# TensorSensor_Driver_DC.net
KiCad netlist of a schematic drawn in Altium Designer
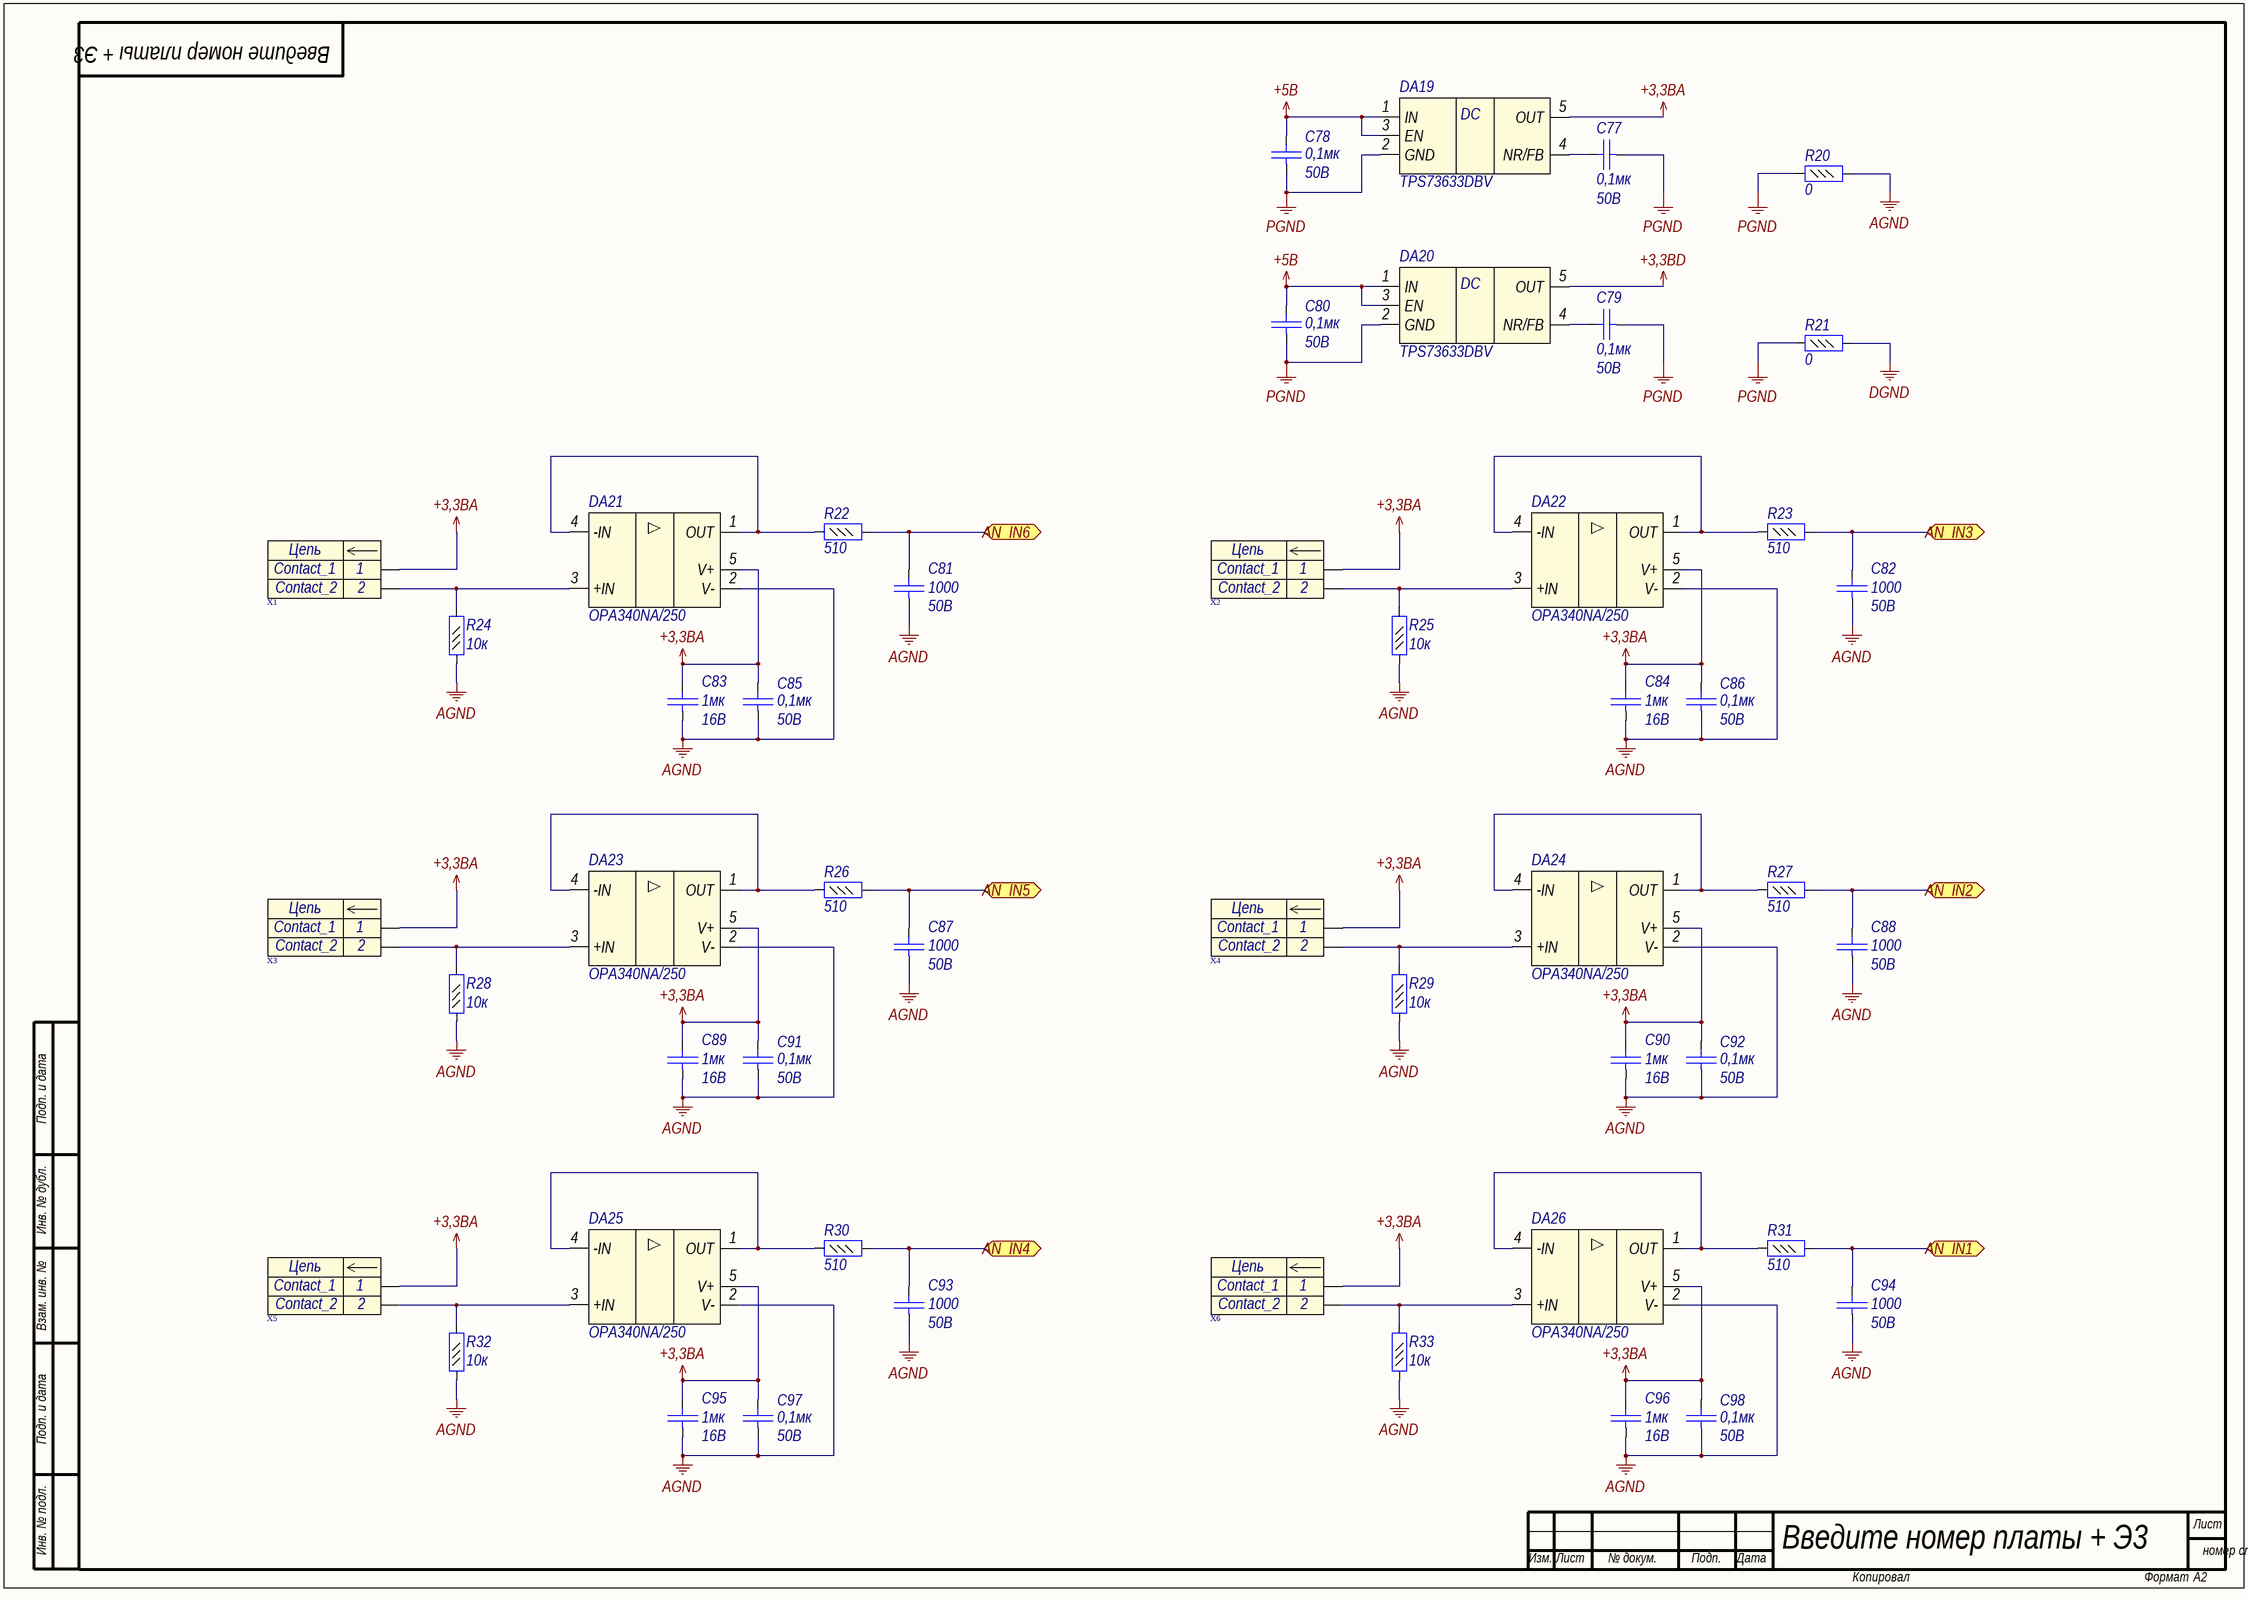
[diagram p0: TensorSensor_Driver&DC.SchDoc]

(export (version "E")
  (design (tool "Eeschema 10.0.6"))
  (components
    (comp (ref "C77")
      (value "0,1мк")
      (footprint "C0603")
      (description "Конденсатор")
      (fields (field (name "VOLTAGE") "50B") (field (name "PART NUMBER") "GRM188R71H104KA93D"))
      (libsource (lib "MOP44") (part "Capacitor"))
    )
    (comp (ref "C78")
      (value "0,1мк")
      (footprint "C0603")
      (description "Конденсатор")
      (fields (field (name "VOLTAGE") "50B") (field (name "PART NUMBER") "GRM188R71H104KA93D"))
      (libsource (lib "MOP44") (part "Capacitor"))
    )
    (comp (ref "C79")
      (value "0,1мк")
      (footprint "C0603")
      (description "Конденсатор")
      (fields (field (name "VOLTAGE") "50B") (field (name "PART NUMBER") "GRM188R71H104KA93D"))
      (libsource (lib "MOP44") (part "Capacitor"))
    )
    (comp (ref "C80")
      (value "0,1мк")
      (footprint "C0603")
      (description "Конденсатор")
      (fields (field (name "VOLTAGE") "50B") (field (name "PART NUMBER") "GRM188R71H104KA93D"))
      (libsource (lib "MOP44") (part "Capacitor"))
    )
    (comp (ref "C81")
      (value "1000")
      (footprint "C0603")
      (description "Конденсатор")
      (fields (field (name "VOLTAGE") "50B") (field (name "PART NUMBER") "GRM1885C1H102J"))
      (libsource (lib "MOP44") (part "Capacitor"))
    )
    (comp (ref "C82")
      (value "1000")
      (footprint "C0603")
      (description "Конденсатор")
      (fields (field (name "VOLTAGE") "50B") (field (name "PART NUMBER") "GRM1885C1H102J"))
      (libsource (lib "MOP44") (part "Capacitor"))
    )
    (comp (ref "C83")
      (value "1мк")
      (footprint "C0603")
      (description "Конденсатор")
      (fields (field (name "VOLTAGE") "16B") (field (name "PART NUMBER") "GRM188R71C105KA12D**"))
      (libsource (lib "MOP44") (part "Capacitor"))
    )
    (comp (ref "C84")
      (value "1мк")
      (footprint "C0603")
      (description "Конденсатор")
      (fields (field (name "VOLTAGE") "16B") (field (name "PART NUMBER") "GRM188R71C105KA12D**"))
      (libsource (lib "MOP44") (part "Capacitor"))
    )
    (comp (ref "C85")
      (value "0,1мк")
      (footprint "C0603")
      (description "Конденсатор")
      (fields (field (name "VOLTAGE") "50B") (field (name "PART NUMBER") "GRM188R71H104KA93D"))
      (libsource (lib "MOP44") (part "Capacitor"))
    )
    (comp (ref "C86")
      (value "0,1мк")
      (footprint "C0603")
      (description "Конденсатор")
      (fields (field (name "VOLTAGE") "50B") (field (name "PART NUMBER") "GRM188R71H104KA93D"))
      (libsource (lib "MOP44") (part "Capacitor"))
    )
    (comp (ref "C87")
      (value "1000")
      (footprint "C0603")
      (description "Конденсатор")
      (fields (field (name "VOLTAGE") "50B") (field (name "PART NUMBER") "GRM1885C1H102J"))
      (libsource (lib "MOP44") (part "Capacitor"))
    )
    (comp (ref "C88")
      (value "1000")
      (footprint "C0603")
      (description "Конденсатор")
      (fields (field (name "VOLTAGE") "50B") (field (name "PART NUMBER") "GRM1885C1H102J"))
      (libsource (lib "MOP44") (part "Capacitor"))
    )
    (comp (ref "C89")
      (value "1мк")
      (footprint "C0603")
      (description "Конденсатор")
      (fields (field (name "VOLTAGE") "16B") (field (name "PART NUMBER") "GRM188R71C105KA12D**"))
      (libsource (lib "MOP44") (part "Capacitor"))
    )
    (comp (ref "C90")
      (value "1мк")
      (footprint "C0603")
      (description "Конденсатор")
      (fields (field (name "VOLTAGE") "16B") (field (name "PART NUMBER") "GRM188R71C105KA12D**"))
      (libsource (lib "MOP44") (part "Capacitor"))
    )
    (comp (ref "C91")
      (value "0,1мк")
      (footprint "C0603")
      (description "Конденсатор")
      (fields (field (name "VOLTAGE") "50B") (field (name "PART NUMBER") "GRM188R71H104KA93D"))
      (libsource (lib "MOP44") (part "Capacitor"))
    )
    (comp (ref "C92")
      (value "0,1мк")
      (footprint "C0603")
      (description "Конденсатор")
      (fields (field (name "VOLTAGE") "50B") (field (name "PART NUMBER") "GRM188R71H104KA93D"))
      (libsource (lib "MOP44") (part "Capacitor"))
    )
    (comp (ref "C93")
      (value "1000")
      (footprint "C0603")
      (description "Конденсатор")
      (fields (field (name "VOLTAGE") "50B") (field (name "PART NUMBER") "GRM1885C1H102J"))
      (libsource (lib "MOP44") (part "Capacitor"))
    )
    (comp (ref "C94")
      (value "1000")
      (footprint "C0603")
      (description "Конденсатор")
      (fields (field (name "VOLTAGE") "50B") (field (name "PART NUMBER") "GRM1885C1H102J"))
      (libsource (lib "MOP44") (part "Capacitor"))
    )
    (comp (ref "C95")
      (value "1мк")
      (footprint "C0603")
      (description "Конденсатор")
      (fields (field (name "VOLTAGE") "16B") (field (name "PART NUMBER") "GRM188R71C105KA12D**"))
      (libsource (lib "MOP44") (part "Capacitor"))
    )
    (comp (ref "C96")
      (value "1мк")
      (footprint "C0603")
      (description "Конденсатор")
      (fields (field (name "VOLTAGE") "16B") (field (name "PART NUMBER") "GRM188R71C105KA12D**"))
      (libsource (lib "MOP44") (part "Capacitor"))
    )
    (comp (ref "C97")
      (value "0,1мк")
      (footprint "C0603")
      (description "Конденсатор")
      (fields (field (name "VOLTAGE") "50B") (field (name "PART NUMBER") "GRM188R71H104KA93D"))
      (libsource (lib "MOP44") (part "Capacitor"))
    )
    (comp (ref "C98")
      (value "0,1мк")
      (footprint "C0603")
      (description "Конденсатор")
      (fields (field (name "VOLTAGE") "50B") (field (name "PART NUMBER") "GRM188R71H104KA93D"))
      (libsource (lib "MOP44") (part "Capacitor"))
    )
    (comp (ref "DA19")
      (value "TPS736DBV")
      (footprint "SOT23-5")
      (description "400-mA Low-Dropout Regulator with Reverse Current  Protection")
      (fields (field (name "PART NUMBER") "TPS73633DBV") (field (name "MANUFACTURER") "Texas Instruments"))
      (libsource (lib "MOP44") (part "TPS736DBV"))
    )
    (comp (ref "DA20")
      (value "TPS736DBV")
      (footprint "SOT23-5")
      (description "400-mA Low-Dropout Regulator with Reverse Current  Protection")
      (fields (field (name "PART NUMBER") "TPS73633DBV") (field (name "MANUFACTURER") "Texas Instruments"))
      (libsource (lib "MOP44") (part "TPS736DBV"))
    )
    (comp (ref "DA21")
      (value "OPA340")
      (footprint "SOT23-5")
      (description "Operational Amplifiers\r\nMicroAmplifier")
      (fields (field (name "PART NUMBER") "OPA340NA/250"))
      (libsource (lib "MOP44") (part "OPA340"))
    )
    (comp (ref "DA22")
      (value "OPA340")
      (footprint "SOT23-5")
      (description "Operational Amplifiers\r\nMicroAmplifier")
      (fields (field (name "PART NUMBER") "OPA340NA/250"))
      (libsource (lib "MOP44") (part "OPA340"))
    )
    (comp (ref "DA23")
      (value "OPA340")
      (footprint "SOT23-5")
      (description "Operational Amplifiers\r\nMicroAmplifier")
      (fields (field (name "PART NUMBER") "OPA340NA/250"))
      (libsource (lib "MOP44") (part "OPA340"))
    )
    (comp (ref "DA24")
      (value "OPA340")
      (footprint "SOT23-5")
      (description "Operational Amplifiers\r\nMicroAmplifier")
      (fields (field (name "PART NUMBER") "OPA340NA/250"))
      (libsource (lib "MOP44") (part "OPA340"))
    )
    (comp (ref "DA25")
      (value "OPA340")
      (footprint "SOT23-5")
      (description "Operational Amplifiers\r\nMicroAmplifier")
      (fields (field (name "PART NUMBER") "OPA340NA/250"))
      (libsource (lib "MOP44") (part "OPA340"))
    )
    (comp (ref "DA26")
      (value "OPA340")
      (footprint "SOT23-5")
      (description "Operational Amplifiers\r\nMicroAmplifier")
      (fields (field (name "PART NUMBER") "OPA340NA/250"))
      (libsource (lib "MOP44") (part "OPA340"))
    )
    (comp (ref "R20")
      (value "0")
      (footprint "R0603")
      (description "Резистор")
      (fields (field (name "PART NUMBER") "RC0603FR-070RL") (field (name "POWER") "0,062Вт"))
      (libsource (lib "MOP44") (part "Resistor_0,062Вт"))
    )
    (comp (ref "R21")
      (value "0")
      (footprint "R0603")
      (description "Резистор")
      (fields (field (name "PART NUMBER") "RC0603FR-070RL") (field (name "POWER") "0,062Вт"))
      (libsource (lib "MOP44") (part "Resistor_0,062Вт"))
    )
    (comp (ref "R22")
      (value "510")
      (footprint "R0603")
      (description "Резистор")
      (fields (field (name "PART NUMBER") "RC0603FR-07510RL") (field (name "POWER") "0,062Вт"))
      (libsource (lib "MOP44") (part "Resistor_0,062Вт"))
    )
    (comp (ref "R23")
      (value "510")
      (footprint "R0603")
      (description "Резистор")
      (fields (field (name "PART NUMBER") "RC0603FR-07510RL") (field (name "POWER") "0,062Вт"))
      (libsource (lib "MOP44") (part "Resistor_0,062Вт"))
    )
    (comp (ref "R24")
      (value "10к")
      (footprint "R0603")
      (description "Резистор")
      (fields (field (name "PART NUMBER") "RC0603FR-0710KL") (field (name "POWER") "0,062Вт"))
      (libsource (lib "") (part "Resistor_0,062Вт_1"))
    )
    (comp (ref "R25")
      (value "10к")
      (footprint "R0603")
      (description "Резистор")
      (fields (field (name "PART NUMBER") "RC0603FR-0710KL") (field (name "POWER") "0,062Вт"))
      (libsource (lib "") (part "Resistor_0,062Вт_1"))
    )
    (comp (ref "R26")
      (value "510")
      (footprint "R0603")
      (description "Резистор")
      (fields (field (name "PART NUMBER") "RC0603FR-07510RL") (field (name "POWER") "0,062Вт"))
      (libsource (lib "MOP44") (part "Resistor_0,062Вт"))
    )
    (comp (ref "R27")
      (value "510")
      (footprint "R0603")
      (description "Резистор")
      (fields (field (name "PART NUMBER") "RC0603FR-07510RL") (field (name "POWER") "0,062Вт"))
      (libsource (lib "MOP44") (part "Resistor_0,062Вт"))
    )
    (comp (ref "R28")
      (value "10к")
      (footprint "R0603")
      (description "Резистор")
      (fields (field (name "PART NUMBER") "RC0603FR-0710KL") (field (name "POWER") "0,062Вт"))
      (libsource (lib "") (part "Resistor_0,062Вт_1"))
    )
    (comp (ref "R29")
      (value "10к")
      (footprint "R0603")
      (description "Резистор")
      (fields (field (name "PART NUMBER") "RC0603FR-0710KL") (field (name "POWER") "0,062Вт"))
      (libsource (lib "") (part "Resistor_0,062Вт_1"))
    )
    (comp (ref "R30")
      (value "510")
      (footprint "R0603")
      (description "Резистор")
      (fields (field (name "PART NUMBER") "RC0603FR-07510RL") (field (name "POWER") "0,062Вт"))
      (libsource (lib "MOP44") (part "Resistor_0,062Вт"))
    )
    (comp (ref "R31")
      (value "510")
      (footprint "R0603")
      (description "Резистор")
      (fields (field (name "PART NUMBER") "RC0603FR-07510RL") (field (name "POWER") "0,062Вт"))
      (libsource (lib "MOP44") (part "Resistor_0,062Вт"))
    )
    (comp (ref "R32")
      (value "10к")
      (footprint "R0603")
      (description "Резистор")
      (fields (field (name "PART NUMBER") "RC0603FR-0710KL") (field (name "POWER") "0,062Вт"))
      (libsource (lib "") (part "Resistor_0,062Вт_1"))
    )
    (comp (ref "R33")
      (value "10к")
      (footprint "R0603")
      (description "Резистор")
      (fields (field (name "PART NUMBER") "RC0603FR-0710KL") (field (name "POWER") "0,062Вт"))
      (libsource (lib "") (part "Resistor_0,062Вт_1"))
    )
    (comp (ref "X1")
      (value "~")
      (footprint "CWF-2")
      (description "Разъем - 2 конт. вилка")
      (fields (field (name "PART NUMBER") "DS1069-2MVW6X"))
      (libsource (lib "MOP44") (part "Header_2_plg"))
    )
    (comp (ref "X2")
      (value "~")
      (footprint "CWF-2")
      (description "Разъем - 2 конт. вилка")
      (fields (field (name "PART NUMBER") "DS1069-2MVW6X"))
      (libsource (lib "MOP44") (part "Header_2_plg"))
    )
    (comp (ref "X3")
      (value "~")
      (footprint "CWF-2")
      (description "Разъем - 2 конт. вилка")
      (fields (field (name "PART NUMBER") "DS1069-2MVW6X"))
      (libsource (lib "MOP44") (part "Header_2_plg"))
    )
    (comp (ref "X4")
      (value "~")
      (footprint "CWF-2")
      (description "Разъем - 2 конт. вилка")
      (fields (field (name "PART NUMBER") "DS1069-2MVW6X"))
      (libsource (lib "MOP44") (part "Header_2_plg"))
    )
    (comp (ref "X5")
      (value "~")
      (footprint "CWF-2")
      (description "Разъем - 2 конт. вилка")
      (fields (field (name "PART NUMBER") "DS1069-2MVW6X"))
      (libsource (lib "MOP44") (part "Header_2_plg"))
    )
    (comp (ref "X6")
      (value "~")
      (footprint "CWF-2")
      (description "Разъем - 2 конт. вилка")
      (fields (field (name "PART NUMBER") "DS1069-2MVW6X"))
      (libsource (lib "MOP44") (part "Header_2_plg"))
    )
  )
  (nets
    (net (code "1") (name "+3,3BA") (class "Default")
      (node (ref "C83") (pin "2") (pinfunction "2_2") (pintype "passive"))
      (node (ref "C84") (pin "2") (pinfunction "2_2") (pintype "passive"))
      (node (ref "C85") (pin "2") (pinfunction "2_2") (pintype "passive"))
      (node (ref "C86") (pin "2") (pinfunction "2_2") (pintype "passive"))
      (node (ref "C89") (pin "2") (pinfunction "2_2") (pintype "passive"))
      (node (ref "C90") (pin "2") (pinfunction "2_2") (pintype "passive"))
      (node (ref "C91") (pin "2") (pinfunction "2_2") (pintype "passive"))
      (node (ref "C92") (pin "2") (pinfunction "2_2") (pintype "passive"))
      (node (ref "C95") (pin "2") (pinfunction "2_2") (pintype "passive"))
      (node (ref "C96") (pin "2") (pinfunction "2_2") (pintype "passive"))
      (node (ref "C97") (pin "2") (pinfunction "2_2") (pintype "passive"))
      (node (ref "C98") (pin "2") (pinfunction "2_2") (pintype "passive"))
      (node (ref "DA19") (pin "5") (pinfunction "OUT_5") (pintype "power_in"))
      (node (ref "DA21") (pin "5") (pinfunction "V+_5") (pintype "passive"))
      (node (ref "DA22") (pin "5") (pinfunction "V+_5") (pintype "passive"))
      (node (ref "DA23") (pin "5") (pinfunction "V+_5") (pintype "passive"))
      (node (ref "DA24") (pin "5") (pinfunction "V+_5") (pintype "passive"))
      (node (ref "DA25") (pin "5") (pinfunction "V+_5") (pintype "passive"))
      (node (ref "DA26") (pin "5") (pinfunction "V+_5") (pintype "passive"))
      (node (ref "X1") (pin "1") (pinfunction "1_1") (pintype "passive"))
      (node (ref "X2") (pin "1") (pinfunction "1_1") (pintype "passive"))
      (node (ref "X3") (pin "1") (pinfunction "1_1") (pintype "passive"))
      (node (ref "X4") (pin "1") (pinfunction "1_1") (pintype "passive"))
      (node (ref "X5") (pin "1") (pinfunction "1_1") (pintype "passive"))
      (node (ref "X6") (pin "1") (pinfunction "1_1") (pintype "passive"))
    )
    (net (code "2") (name "+3,3BD") (class "Default")
      (node (ref "DA20") (pin "5") (pinfunction "OUT_5") (pintype "power_in"))
    )
    (net (code "3") (name "+5B") (class "Default")
      (node (ref "C78") (pin "2") (pinfunction "2_2") (pintype "passive"))
      (node (ref "C80") (pin "2") (pinfunction "2_2") (pintype "passive"))
      (node (ref "DA19") (pin "1") (pinfunction "IN_1") (pintype "power_in"))
      (node (ref "DA19") (pin "3") (pinfunction "EN_3") (pintype "power_in"))
      (node (ref "DA20") (pin "1") (pinfunction "IN_1") (pintype "power_in"))
      (node (ref "DA20") (pin "3") (pinfunction "EN_3") (pintype "power_in"))
    )
    (net (code "4") (name "/AN_IN1") (class "Default")
      (node (ref "C94") (pin "2") (pinfunction "2_2") (pintype "passive"))
      (node (ref "R31") (pin "2") (pinfunction "2_2") (pintype "passive"))
    )
    (net (code "5") (name "/AN_IN2") (class "Default")
      (node (ref "C88") (pin "2") (pinfunction "2_2") (pintype "passive"))
      (node (ref "R27") (pin "2") (pinfunction "2_2") (pintype "passive"))
    )
    (net (code "6") (name "/AN_IN3") (class "Default")
      (node (ref "C82") (pin "2") (pinfunction "2_2") (pintype "passive"))
      (node (ref "R23") (pin "2") (pinfunction "2_2") (pintype "passive"))
    )
    (net (code "7") (name "/AN_IN4") (class "Default")
      (node (ref "C93") (pin "2") (pinfunction "2_2") (pintype "passive"))
      (node (ref "R30") (pin "2") (pinfunction "2_2") (pintype "passive"))
    )
    (net (code "8") (name "/AN_IN5") (class "Default")
      (node (ref "C87") (pin "2") (pinfunction "2_2") (pintype "passive"))
      (node (ref "R26") (pin "2") (pinfunction "2_2") (pintype "passive"))
    )
    (net (code "9") (name "/AN_IN6") (class "Default")
      (node (ref "C81") (pin "2") (pinfunction "2_2") (pintype "passive"))
      (node (ref "R22") (pin "2") (pinfunction "2_2") (pintype "passive"))
    )
    (net (code "10") (name "AGND") (class "Default")
      (node (ref "C81") (pin "1") (pinfunction "1_1") (pintype "passive"))
      (node (ref "C82") (pin "1") (pinfunction "1_1") (pintype "passive"))
      (node (ref "C83") (pin "1") (pinfunction "1_1") (pintype "passive"))
      (node (ref "C84") (pin "1") (pinfunction "1_1") (pintype "passive"))
      (node (ref "C85") (pin "1") (pinfunction "1_1") (pintype "passive"))
      (node (ref "C86") (pin "1") (pinfunction "1_1") (pintype "passive"))
      (node (ref "C87") (pin "1") (pinfunction "1_1") (pintype "passive"))
      (node (ref "C88") (pin "1") (pinfunction "1_1") (pintype "passive"))
      (node (ref "C89") (pin "1") (pinfunction "1_1") (pintype "passive"))
      (node (ref "C90") (pin "1") (pinfunction "1_1") (pintype "passive"))
      (node (ref "C91") (pin "1") (pinfunction "1_1") (pintype "passive"))
      (node (ref "C92") (pin "1") (pinfunction "1_1") (pintype "passive"))
      (node (ref "C93") (pin "1") (pinfunction "1_1") (pintype "passive"))
      (node (ref "C94") (pin "1") (pinfunction "1_1") (pintype "passive"))
      (node (ref "C95") (pin "1") (pinfunction "1_1") (pintype "passive"))
      (node (ref "C96") (pin "1") (pinfunction "1_1") (pintype "passive"))
      (node (ref "C97") (pin "1") (pinfunction "1_1") (pintype "passive"))
      (node (ref "C98") (pin "1") (pinfunction "1_1") (pintype "passive"))
      (node (ref "DA21") (pin "2") (pinfunction "V-_2") (pintype "passive"))
      (node (ref "DA22") (pin "2") (pinfunction "V-_2") (pintype "passive"))
      (node (ref "DA23") (pin "2") (pinfunction "V-_2") (pintype "passive"))
      (node (ref "DA24") (pin "2") (pinfunction "V-_2") (pintype "passive"))
      (node (ref "DA25") (pin "2") (pinfunction "V-_2") (pintype "passive"))
      (node (ref "DA26") (pin "2") (pinfunction "V-_2") (pintype "passive"))
      (node (ref "R20") (pin "2") (pinfunction "2_2") (pintype "passive"))
      (node (ref "R24") (pin "1") (pinfunction "1_1") (pintype "passive"))
      (node (ref "R25") (pin "1") (pinfunction "1_1") (pintype "passive"))
      (node (ref "R28") (pin "1") (pinfunction "1_1") (pintype "passive"))
      (node (ref "R29") (pin "1") (pinfunction "1_1") (pintype "passive"))
      (node (ref "R32") (pin "1") (pinfunction "1_1") (pintype "passive"))
      (node (ref "R33") (pin "1") (pinfunction "1_1") (pintype "passive"))
    )
    (net (code "11") (name "DGND") (class "Default")
      (node (ref "R21") (pin "2") (pinfunction "2_2") (pintype "passive"))
    )
    (net (code "12") (name "Net-(DA19-NR{slash}FB)") (class "Default")
      (node (ref "C77") (pin "2") (pinfunction "2_2") (pintype "passive"))
      (node (ref "DA19") (pin "4") (pinfunction "NR/FB_4") (pintype "power_in"))
    )
    (net (code "13") (name "Net-(DA20-NR{slash}FB)") (class "Default")
      (node (ref "C79") (pin "2") (pinfunction "2_2") (pintype "passive"))
      (node (ref "DA20") (pin "4") (pinfunction "NR/FB_4") (pintype "power_in"))
    )
    (net (code "14") (name "Net-(DA21-+IN)") (class "Default")
      (node (ref "DA21") (pin "3") (pinfunction "+IN_3") (pintype "passive"))
      (node (ref "R24") (pin "2") (pinfunction "2_2") (pintype "passive"))
      (node (ref "X1") (pin "2") (pinfunction "2_2") (pintype "passive"))
    )
    (net (code "15") (name "Net-(DA21--IN)") (class "Default")
      (node (ref "DA21") (pin "1") (pinfunction "OUT_1") (pintype "passive"))
      (node (ref "DA21") (pin "4") (pinfunction "-IN_4") (pintype "passive"))
      (node (ref "R22") (pin "1") (pinfunction "1_1") (pintype "passive"))
    )
    (net (code "16") (name "Net-(DA22-+IN)") (class "Default")
      (node (ref "DA22") (pin "3") (pinfunction "+IN_3") (pintype "passive"))
      (node (ref "R25") (pin "2") (pinfunction "2_2") (pintype "passive"))
      (node (ref "X2") (pin "2") (pinfunction "2_2") (pintype "passive"))
    )
    (net (code "17") (name "Net-(DA22--IN)") (class "Default")
      (node (ref "DA22") (pin "1") (pinfunction "OUT_1") (pintype "passive"))
      (node (ref "DA22") (pin "4") (pinfunction "-IN_4") (pintype "passive"))
      (node (ref "R23") (pin "1") (pinfunction "1_1") (pintype "passive"))
    )
    (net (code "18") (name "Net-(DA23-+IN)") (class "Default")
      (node (ref "DA23") (pin "3") (pinfunction "+IN_3") (pintype "passive"))
      (node (ref "R28") (pin "2") (pinfunction "2_2") (pintype "passive"))
      (node (ref "X3") (pin "2") (pinfunction "2_2") (pintype "passive"))
    )
    (net (code "19") (name "Net-(DA23--IN)") (class "Default")
      (node (ref "DA23") (pin "1") (pinfunction "OUT_1") (pintype "passive"))
      (node (ref "DA23") (pin "4") (pinfunction "-IN_4") (pintype "passive"))
      (node (ref "R26") (pin "1") (pinfunction "1_1") (pintype "passive"))
    )
    (net (code "20") (name "Net-(DA24-+IN)") (class "Default")
      (node (ref "DA24") (pin "3") (pinfunction "+IN_3") (pintype "passive"))
      (node (ref "R29") (pin "2") (pinfunction "2_2") (pintype "passive"))
      (node (ref "X4") (pin "2") (pinfunction "2_2") (pintype "passive"))
    )
    (net (code "21") (name "Net-(DA24--IN)") (class "Default")
      (node (ref "DA24") (pin "1") (pinfunction "OUT_1") (pintype "passive"))
      (node (ref "DA24") (pin "4") (pinfunction "-IN_4") (pintype "passive"))
      (node (ref "R27") (pin "1") (pinfunction "1_1") (pintype "passive"))
    )
    (net (code "22") (name "Net-(DA25-+IN)") (class "Default")
      (node (ref "DA25") (pin "3") (pinfunction "+IN_3") (pintype "passive"))
      (node (ref "R32") (pin "2") (pinfunction "2_2") (pintype "passive"))
      (node (ref "X5") (pin "2") (pinfunction "2_2") (pintype "passive"))
    )
    (net (code "23") (name "Net-(DA25--IN)") (class "Default")
      (node (ref "DA25") (pin "1") (pinfunction "OUT_1") (pintype "passive"))
      (node (ref "DA25") (pin "4") (pinfunction "-IN_4") (pintype "passive"))
      (node (ref "R30") (pin "1") (pinfunction "1_1") (pintype "passive"))
    )
    (net (code "24") (name "Net-(DA26-+IN)") (class "Default")
      (node (ref "DA26") (pin "3") (pinfunction "+IN_3") (pintype "passive"))
      (node (ref "R33") (pin "2") (pinfunction "2_2") (pintype "passive"))
      (node (ref "X6") (pin "2") (pinfunction "2_2") (pintype "passive"))
    )
    (net (code "25") (name "Net-(DA26--IN)") (class "Default")
      (node (ref "DA26") (pin "1") (pinfunction "OUT_1") (pintype "passive"))
      (node (ref "DA26") (pin "4") (pinfunction "-IN_4") (pintype "passive"))
      (node (ref "R31") (pin "1") (pinfunction "1_1") (pintype "passive"))
    )
    (net (code "26") (name "PGND") (class "Default")
      (node (ref "C77") (pin "1") (pinfunction "1_1") (pintype "passive"))
      (node (ref "C78") (pin "1") (pinfunction "1_1") (pintype "passive"))
      (node (ref "C79") (pin "1") (pinfunction "1_1") (pintype "passive"))
      (node (ref "C80") (pin "1") (pinfunction "1_1") (pintype "passive"))
      (node (ref "DA19") (pin "2") (pinfunction "GND_2") (pintype "power_in"))
      (node (ref "DA20") (pin "2") (pinfunction "GND_2") (pintype "power_in"))
      (node (ref "R20") (pin "1") (pinfunction "1_1") (pintype "passive"))
      (node (ref "R21") (pin "1") (pinfunction "1_1") (pintype "passive"))
    )
  )
)
